# Nano-CC-EL_0v6_1_ENP252-17.net
KiCad netlist of a schematic drawn in EAGLE
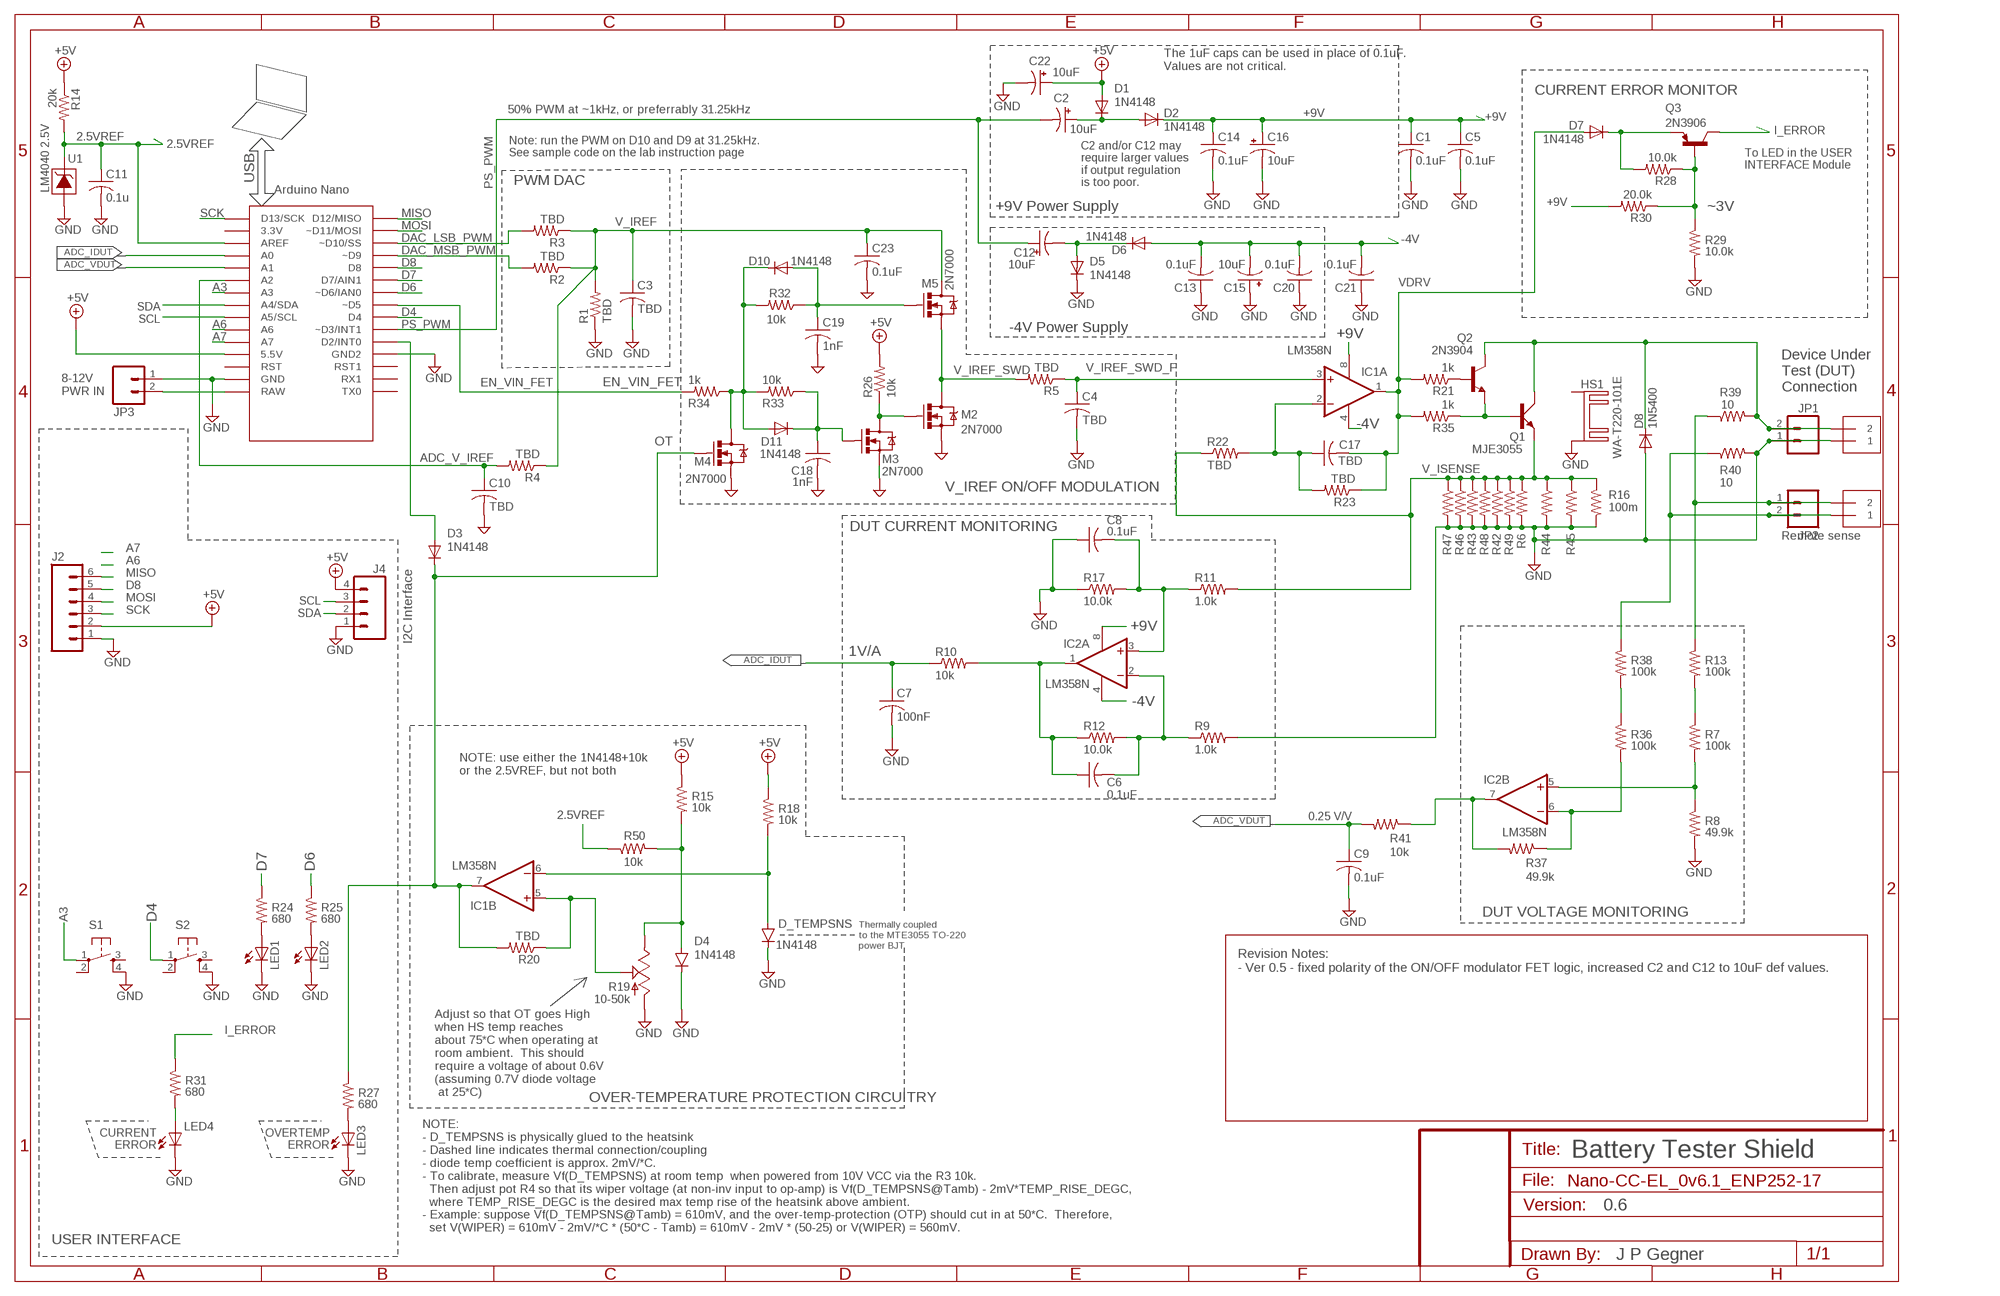
[diagram p0: schematic, sheet 1]

(export (version "E")
  (design (tool "Eeschema 10.0.6"))
  (components
    (comp (ref "C1")
      (value "0.1uF")
      (footprint "eagle-import:C025-025X050")
      (libsource (lib "eagle-import") (part "C-US025-025X050"))
    )
    (comp (ref "C2")
      (value "10uF")
      (footprint "eagle-import:E5-5")
      (libsource (lib "eagle-import") (part "CPOL-USE5-5"))
    )
    (comp (ref "C3")
      (value "TBD")
      (footprint "eagle-import:C025-025X050")
      (libsource (lib "eagle-import") (part "C-US025-025X050"))
    )
    (comp (ref "C4")
      (value "TBD")
      (footprint "eagle-import:C025-025X050")
      (libsource (lib "eagle-import") (part "C-US025-025X050"))
    )
    (comp (ref "C5")
      (value "0.1uF")
      (footprint "eagle-import:C025-025X050")
      (libsource (lib "eagle-import") (part "C-US025-025X050"))
    )
    (comp (ref "C6")
      (value "0.1uF")
      (footprint "eagle-import:C025-025X050")
      (libsource (lib "eagle-import") (part "C-US025-025X050"))
    )
    (comp (ref "C7")
      (value "100nF")
      (footprint "eagle-import:C025-024X044")
      (libsource (lib "eagle-import") (part "C-US025-024X044"))
    )
    (comp (ref "C8")
      (value "0.1uF")
      (footprint "eagle-import:C025-025X050")
      (libsource (lib "eagle-import") (part "C-US025-025X050"))
    )
    (comp (ref "C9")
      (value "0.1uF")
      (footprint "eagle-import:C025-025X050")
      (libsource (lib "eagle-import") (part "C-US025-025X050"))
    )
    (comp (ref "C10")
      (value "TBD")
      (footprint "eagle-import:C025-025X050")
      (libsource (lib "eagle-import") (part "C-US025-025X050"))
    )
    (comp (ref "C11")
      (value "0.1u")
      (footprint "eagle-import:C025-025X050")
      (libsource (lib "eagle-import") (part "C-US025-025X050"))
    )
    (comp (ref "C12")
      (value "10uF")
      (footprint "eagle-import:E5-5")
      (libsource (lib "eagle-import") (part "CPOL-USE5-5"))
    )
    (comp (ref "C13")
      (value "0.1uF")
      (footprint "eagle-import:C025-025X050")
      (libsource (lib "eagle-import") (part "C-US025-025X050"))
    )
    (comp (ref "C14")
      (value "0.1uF")
      (footprint "eagle-import:C025-025X050")
      (libsource (lib "eagle-import") (part "C-US025-025X050"))
    )
    (comp (ref "C15")
      (value "10uF")
      (footprint "eagle-import:E5-5")
      (libsource (lib "eagle-import") (part "CPOL-USE5-5"))
    )
    (comp (ref "C16")
      (value "10uF")
      (footprint "eagle-import:E5-5")
      (libsource (lib "eagle-import") (part "CPOL-USE5-5"))
    )
    (comp (ref "C17")
      (value "TBD")
      (footprint "eagle-import:C025-025X050")
      (libsource (lib "eagle-import") (part "C-US025-025X050"))
    )
    (comp (ref "C18")
      (value "1nF")
      (footprint "eagle-import:C025-025X050")
      (libsource (lib "eagle-import") (part "C-US025-025X050"))
    )
    (comp (ref "C19")
      (value "1nF")
      (footprint "eagle-import:C025-025X050")
      (libsource (lib "eagle-import") (part "C-US025-025X050"))
    )
    (comp (ref "C20")
      (value "0.1uF")
      (footprint "eagle-import:C025-025X050")
      (libsource (lib "eagle-import") (part "C-US025-025X050"))
    )
    (comp (ref "C21")
      (value "0.1uF")
      (footprint "eagle-import:C025-025X050")
      (libsource (lib "eagle-import") (part "C-US025-025X050"))
    )
    (comp (ref "C22")
      (value "10uF")
      (footprint "eagle-import:E5-5")
      (libsource (lib "eagle-import") (part "CPOL-USE5-5"))
    )
    (comp (ref "C23")
      (value "0.1uF")
      (footprint "eagle-import:C025-025X050")
      (libsource (lib "eagle-import") (part "C-US025-025X050"))
    )
    (comp (ref "D1")
      (value "1N4148")
      (footprint "eagle-import:0207_2V-D")
      (libsource (lib "eagle-import") (part "1N4148"))
    )
    (comp (ref "D2")
      (value "1N4148")
      (footprint "eagle-import:0207_2V-D")
      (libsource (lib "eagle-import") (part "1N4148"))
    )
    (comp (ref "D3")
      (value "1N4148")
      (footprint "eagle-import:0207_2V-D")
      (libsource (lib "eagle-import") (part "1N4148"))
    )
    (comp (ref "D4")
      (value "1N4148")
      (footprint "eagle-import:0207_2V-D")
      (libsource (lib "eagle-import") (part "ideal_elements_1N4148"))
    )
    (comp (ref "D5")
      (value "1N4148")
      (footprint "eagle-import:0207_2V-D")
      (libsource (lib "eagle-import") (part "1N4148"))
    )
    (comp (ref "D6")
      (value "1N4148")
      (footprint "eagle-import:0207_2V-D")
      (libsource (lib "eagle-import") (part "1N4148"))
    )
    (comp (ref "D7")
      (value "1N4148")
      (footprint "eagle-import:0207_2V-D")
      (libsource (lib "eagle-import") (part "1N4148"))
    )
    (comp (ref "D8")
      (value "1N5400")
      (footprint "eagle-import:DO201-15")
      (libsource (lib "eagle-import") (part "1N5400"))
    )
    (comp (ref "D10")
      (value "1N4148")
      (footprint "eagle-import:0207_2V-D")
      (libsource (lib "eagle-import") (part "1N4148"))
    )
    (comp (ref "D11")
      (value "1N4148")
      (footprint "eagle-import:0207_2V-D")
      (libsource (lib "eagle-import") (part "1N4148"))
    )
    (comp (ref "D_TEMPSNS")
      (value "1N4148")
      (footprint "eagle-import:0207_2V-D")
      (libsource (lib "eagle-import") (part "ideal_elements_1N4148"))
    )
    (comp (ref "HS1")
      (value "WA-T220-101E")
      (footprint "eagle-import:WX-T220-101E")
      (libsource (lib "eagle-import") (part "WA-T220-101E"))
    )
    (comp (ref "IC1")
      (value "LM358N")
      (footprint "eagle-import:DIL08")
      (libsource (lib "eagle-import") (part "LM358N"))
    )
    (comp (ref "IC2")
      (value "LM358N")
      (footprint "eagle-import:DIL08")
      (libsource (lib "eagle-import") (part "LM358N"))
    )
    (comp (ref "J2")
      (value "M06POLAR")
      (footprint "eagle-import:MOLEX-1X6")
      (libsource (lib "eagle-import") (part "M06POLAR"))
    )
    (comp (ref "J4")
      (value "M04LOCK_LONGPADS")
      (footprint "eagle-import:1X04_LOCK_LONGPADS")
      (libsource (lib "eagle-import") (part "M04LOCK_LONGPADS"))
    )
    (comp (ref "JP1")
      (value "M02PTH")
      (footprint "eagle-import:1X02")
      (libsource (lib "eagle-import") (part "M02PTH"))
    )
    (comp (ref "JP2")
      (value "M02PTH")
      (footprint "eagle-import:1X02")
      (libsource (lib "eagle-import") (part "M02PTH"))
    )
    (comp (ref "JP3")
      (value "M02PTH")
      (footprint "eagle-import:1X02")
      (libsource (lib "eagle-import") (part "M02PTH"))
    )
    (comp (ref "JP4")
      (value "1X2-3.5MM")
      (footprint "eagle-import:1X2-3.5MM")
      (libsource (lib "eagle-import") (part "1X2-3.5MM"))
    )
    (comp (ref "JP5")
      (value "1X2-3.5MM")
      (footprint "eagle-import:1X2-3.5MM")
      (libsource (lib "eagle-import") (part "1X2-3.5MM"))
    )
    (comp (ref "LED1")
      (value "LED-3MM-NO_SILK")
      (footprint "eagle-import:LED3MM-NS")
      (libsource (lib "eagle-import") (part "LED-3MM-NO_SILK"))
    )
    (comp (ref "LED2")
      (value "LED-3MM-NO_SILK")
      (footprint "eagle-import:LED3MM-NS")
      (libsource (lib "eagle-import") (part "LED-3MM-NO_SILK"))
    )
    (comp (ref "LED3")
      (value "LED-3MM-NO_SILK")
      (footprint "eagle-import:LED3MM-NS")
      (libsource (lib "eagle-import") (part "LED-3MM-NO_SILK"))
    )
    (comp (ref "LED4")
      (value "LED-3MM-NO_SILK")
      (footprint "eagle-import:LED3MM-NS")
      (libsource (lib "eagle-import") (part "LED-3MM-NO_SILK"))
    )
    (comp (ref "M2")
      (value "2N7000")
      (footprint "eagle-import:TO-92")
      (libsource (lib "eagle-import") (part "MOSFET-NCHANNEL2N7000"))
    )
    (comp (ref "M3")
      (value "2N7000")
      (footprint "eagle-import:TO-92")
      (libsource (lib "eagle-import") (part "MOSFET-NCHANNEL2N7000"))
    )
    (comp (ref "M4")
      (value "2N7000")
      (footprint "eagle-import:TO-92")
      (libsource (lib "eagle-import") (part "MOSFET-NCHANNEL2N7000"))
    )
    (comp (ref "M5")
      (value "2N7000")
      (footprint "eagle-import:TO-92")
      (libsource (lib "eagle-import") (part "MOSFET-NCHANNEL2N7000"))
    )
    (comp (ref "Q1")
      (value "MJE3055")
      (footprint "eagle-import:TO220AV")
      (libsource (lib "eagle-import") (part "MJE3055"))
    )
    (comp (ref "Q2")
      (value "2N3904")
      (footprint "eagle-import:TO92")
      (libsource (lib "eagle-import") (part "2N3904"))
    )
    (comp (ref "Q3")
      (value "2N3906")
      (footprint "eagle-import:TO92")
      (libsource (lib "eagle-import") (part "2N3906"))
    )
    (comp (ref "R1")
      (value "TBD")
      (footprint "eagle-import:0204_7")
      (libsource (lib "eagle-import") (part "R-US_0204/7"))
    )
    (comp (ref "R2")
      (value "TBD")
      (footprint "eagle-import:0204_7")
      (libsource (lib "eagle-import") (part "R-US_0204/7"))
    )
    (comp (ref "R3")
      (value "TBD")
      (footprint "eagle-import:0204_7")
      (libsource (lib "eagle-import") (part "R-US_0204/7"))
    )
    (comp (ref "R4")
      (value "TBD")
      (footprint "eagle-import:0204_7")
      (libsource (lib "eagle-import") (part "R-US_0204/7"))
    )
    (comp (ref "R5")
      (value "TBD")
      (footprint "eagle-import:0204V")
      (libsource (lib "eagle-import") (part "R-US_0204/2V"))
    )
    (comp (ref "R6")
      (value "100m")
      (footprint "eagle-import:0204_7")
      (libsource (lib "eagle-import") (part "R-US_0204/7"))
    )
    (comp (ref "R7")
      (value "100k")
      (footprint "eagle-import:0204_7")
      (libsource (lib "eagle-import") (part "R-US_0204/7"))
    )
    (comp (ref "R8")
      (value "49.9k")
      (footprint "eagle-import:0204_7")
      (libsource (lib "eagle-import") (part "R-US_0204/7"))
    )
    (comp (ref "R9")
      (value "1.0k")
      (footprint "eagle-import:0204_7")
      (libsource (lib "eagle-import") (part "R-US_0204/7"))
    )
    (comp (ref "R10")
      (value "10k")
      (footprint "eagle-import:0204_7")
      (libsource (lib "eagle-import") (part "R-US_0204/7"))
    )
    (comp (ref "R11")
      (value "1.0k")
      (footprint "eagle-import:0204_7")
      (libsource (lib "eagle-import") (part "R-US_0204/7"))
    )
    (comp (ref "R12")
      (value "10.0k")
      (footprint "eagle-import:0204V")
      (libsource (lib "eagle-import") (part "R-US_0204/2V"))
    )
    (comp (ref "R13")
      (value "100k")
      (footprint "eagle-import:0204_7")
      (libsource (lib "eagle-import") (part "R-US_0204/7"))
    )
    (comp (ref "R14")
      (value "20k")
      (footprint "eagle-import:0204_7")
      (libsource (lib "eagle-import") (part "R-US_0204/7"))
    )
    (comp (ref "R15")
      (value "10k")
      (footprint "eagle-import:0204_7")
      (libsource (lib "eagle-import") (part "R-US_0204/7"))
    )
    (comp (ref "R16")
      (value "100m")
      (footprint "eagle-import:0204_7")
      (libsource (lib "eagle-import") (part "R-US_0204/7"))
    )
    (comp (ref "R17")
      (value "10.0k")
      (footprint "eagle-import:0204_7")
      (libsource (lib "eagle-import") (part "R-US_0204/7"))
    )
    (comp (ref "R18")
      (value "10k")
      (footprint "eagle-import:0204_7")
      (libsource (lib "eagle-import") (part "R-US_0204/7"))
    )
    (comp (ref "R19")
      (value "10-50k")
      (footprint "eagle-import:B64Y")
      (libsource (lib "eagle-import") (part "TRIM_US-B64Y"))
    )
    (comp (ref "R20")
      (value "TBD")
      (footprint "eagle-import:0204_7")
      (libsource (lib "eagle-import") (part "R-US_0204/7"))
    )
    (comp (ref "R21")
      (value "1k")
      (footprint "eagle-import:0204_7")
      (libsource (lib "eagle-import") (part "R-US_0204/7"))
    )
    (comp (ref "R22")
      (value "TBD")
      (footprint "eagle-import:0204_7")
      (libsource (lib "eagle-import") (part "R-US_0204/7"))
    )
    (comp (ref "R23")
      (value "TBD")
      (footprint "eagle-import:0204V")
      (libsource (lib "eagle-import") (part "R-US_0204/2V"))
    )
    (comp (ref "R24")
      (value "680")
      (footprint "eagle-import:0204_7")
      (libsource (lib "eagle-import") (part "R-US_0204/7"))
    )
    (comp (ref "R25")
      (value "680")
      (footprint "eagle-import:0204_7")
      (libsource (lib "eagle-import") (part "R-US_0204/7"))
    )
    (comp (ref "R26")
      (value "10k")
      (footprint "eagle-import:0204_7")
      (libsource (lib "eagle-import") (part "R-US_0204/7"))
    )
    (comp (ref "R27")
      (value "680")
      (footprint "eagle-import:0204_7")
      (libsource (lib "eagle-import") (part "R-US_0204/7"))
    )
    (comp (ref "R28")
      (value "10.0k")
      (footprint "eagle-import:0204_7")
      (libsource (lib "eagle-import") (part "R-US_0204/7"))
    )
    (comp (ref "R29")
      (value "10.0k")
      (footprint "eagle-import:0204_7")
      (libsource (lib "eagle-import") (part "R-US_0204/7"))
    )
    (comp (ref "R30")
      (value "20.0k")
      (footprint "eagle-import:0204_7")
      (libsource (lib "eagle-import") (part "R-US_0204/7"))
    )
    (comp (ref "R31")
      (value "680")
      (footprint "eagle-import:0204_7")
      (libsource (lib "eagle-import") (part "R-US_0204/7"))
    )
    (comp (ref "R32")
      (value "10k")
      (footprint "eagle-import:0204_7")
      (libsource (lib "eagle-import") (part "R-US_0204/7"))
    )
    (comp (ref "R33")
      (value "10k")
      (footprint "eagle-import:0204_7")
      (libsource (lib "eagle-import") (part "R-US_0204/7"))
    )
    (comp (ref "R34")
      (value "1k")
      (footprint "eagle-import:0204V")
      (libsource (lib "eagle-import") (part "R-US_0204/2V"))
    )
    (comp (ref "R35")
      (value "1k")
      (footprint "eagle-import:0204_7")
      (libsource (lib "eagle-import") (part "R-US_0204/7"))
    )
    (comp (ref "R36")
      (value "100k")
      (footprint "eagle-import:0204_7")
      (libsource (lib "eagle-import") (part "R-US_0204/7"))
    )
    (comp (ref "R37")
      (value "49.9k")
      (footprint "eagle-import:0204V")
      (libsource (lib "eagle-import") (part "R-US_0204/2V"))
    )
    (comp (ref "R38")
      (value "100k")
      (footprint "eagle-import:0204_7")
      (libsource (lib "eagle-import") (part "R-US_0204/7"))
    )
    (comp (ref "R39")
      (value "10")
      (footprint "eagle-import:0204V")
      (libsource (lib "eagle-import") (part "R-US_0204/2V"))
    )
    (comp (ref "R40")
      (value "10")
      (footprint "eagle-import:0204V")
      (libsource (lib "eagle-import") (part "R-US_0204/2V"))
    )
    (comp (ref "R41")
      (value "10k")
      (footprint "eagle-import:0204_7")
      (libsource (lib "eagle-import") (part "R-US_0204/7"))
    )
    (comp (ref "R42")
      (value "100m")
      (footprint "eagle-import:0204_7")
      (libsource (lib "eagle-import") (part "R-US_0204/7"))
    )
    (comp (ref "R43")
      (value "100m")
      (footprint "eagle-import:0204_7")
      (libsource (lib "eagle-import") (part "R-US_0204/7"))
    )
    (comp (ref "R44")
      (value "100m")
      (footprint "eagle-import:0204_7")
      (libsource (lib "eagle-import") (part "R-US_0204/7"))
    )
    (comp (ref "R45")
      (value "100m")
      (footprint "eagle-import:0204_7")
      (libsource (lib "eagle-import") (part "R-US_0204/7"))
    )
    (comp (ref "R46")
      (value "100m")
      (footprint "eagle-import:0204_7")
      (libsource (lib "eagle-import") (part "R-US_0204/7"))
    )
    (comp (ref "R47")
      (value "100m")
      (footprint "eagle-import:0204_7")
      (libsource (lib "eagle-import") (part "R-US_0204/7"))
    )
    (comp (ref "R48")
      (value "100m")
      (footprint "eagle-import:0204_7")
      (libsource (lib "eagle-import") (part "R-US_0204/7"))
    )
    (comp (ref "R49")
      (value "100m")
      (footprint "eagle-import:0204_7")
      (libsource (lib "eagle-import") (part "R-US_0204/7"))
    )
    (comp (ref "R50")
      (value "10k")
      (footprint "eagle-import:0204_7")
      (libsource (lib "eagle-import") (part "R-US_0204/7"))
    )
    (comp (ref "S1")
      (value "E-SWITCH_TL1105L-F250-Q")
      (footprint "eagle-import:OMRON_B3F-1XX-JPGMOD")
      (libsource (lib "eagle-import") (part "E-SWITCH_TL1105L-F250-Q"))
    )
    (comp (ref "S2")
      (value "E-SWITCH_TL1105L-F250-Q")
      (footprint "eagle-import:OMRON_B3F-1XX-JPGMOD")
      (libsource (lib "eagle-import") (part "E-SWITCH_TL1105L-F250-Q"))
    )
    (comp (ref "U$1")
      (value "NANO")
      (footprint "eagle-import:NANO")
      (libsource (lib "eagle-import") (part "NANO"))
    )
    (comp (ref "U1")
      (value "LM4040 2.5V")
      (footprint "eagle-import:TO92")
      (libsource (lib "eagle-import") (part "LM4040TO92"))
    )
  )
  (nets
    (net (code "1") (name "+5V") (class "Default")
      (node (ref "C22") (pin "+") (pinfunction "+_+") (pintype "passive"))
      (node (ref "D1") (pin "A") (pinfunction "A_A") (pintype "passive"))
      (node (ref "J2") (pin "2") (pinfunction "2_2") (pintype "passive"))
      (node (ref "J4") (pin "4") (pinfunction "4_4") (pintype "passive"))
      (node (ref "R14") (pin "1") (pinfunction "1_1") (pintype "passive"))
      (node (ref "R15") (pin "1") (pinfunction "1_1") (pintype "passive"))
      (node (ref "R18") (pin "1") (pinfunction "1_1") (pintype "passive"))
      (node (ref "R26") (pin "2") (pinfunction "2_2") (pintype "passive"))
      (node (ref "U$1") (pin "5V") (pinfunction "5.5V_5V") (pintype "bidirectional"))
    )
    (net (code "2") (name "/+9V") (class "Default")
      (node (ref "C1") (pin "1") (pinfunction "1_1") (pintype "passive"))
      (node (ref "C14") (pin "1") (pinfunction "1_1") (pintype "passive"))
      (node (ref "C16") (pin "+") (pinfunction "+_+") (pintype "passive"))
      (node (ref "C5") (pin "1") (pinfunction "1_1") (pintype "passive"))
      (node (ref "D2") (pin "K") (pinfunction "C_K") (pintype "passive"))
      (node (ref "IC1") (pin "8") (pinfunction "V+_8") (pintype "power_in"))
      (node (ref "IC2") (pin "8") (pinfunction "V+_8") (pintype "power_in"))
      (node (ref "R30") (pin "2") (pinfunction "2_2") (pintype "passive"))
    )
    (net (code "3") (name "/-4V") (class "Default")
      (node (ref "C13") (pin "2") (pinfunction "2_2") (pintype "passive"))
      (node (ref "C15") (pin "-") (pinfunction "-_-") (pintype "passive"))
      (node (ref "C20") (pin "2") (pinfunction "2_2") (pintype "passive"))
      (node (ref "C21") (pin "2") (pinfunction "2_2") (pintype "passive"))
      (node (ref "D6") (pin "A") (pinfunction "A_A") (pintype "passive"))
      (node (ref "IC1") (pin "4") (pinfunction "V-_4") (pintype "power_in"))
      (node (ref "IC2") (pin "4") (pinfunction "V-_4") (pintype "power_in"))
    )
    (net (code "4") (name "/2.5VREF") (class "Default")
      (node (ref "C11") (pin "1") (pinfunction "1_1") (pintype "passive"))
      (node (ref "R14") (pin "2") (pinfunction "2_2") (pintype "passive"))
      (node (ref "R50") (pin "1") (pinfunction "1_1") (pintype "passive"))
      (node (ref "U$1") (pin "AREF") (pinfunction "AREF_AREF") (pintype "bidirectional"))
      (node (ref "U1") (pin "2") (pinfunction "CATHODE_2") (pintype "passive"))
    )
    (net (code "5") (name "/A3") (class "Default")
      (node (ref "S1") (pin "1") (pinfunction "P_1") (pintype "passive"))
      (node (ref "U$1") (pin "A3") (pinfunction "A3_A3") (pintype "bidirectional"))
    )
    (net (code "6") (name "/A6") (class "Default")
      (node (ref "U$1") (pin "A6") (pinfunction "A6_A6") (pintype "bidirectional"))
    )
    (net (code "7") (name "/A7") (class "Default")
      (node (ref "U$1") (pin "A7") (pinfunction "A7_A7") (pintype "bidirectional"))
    )
    (net (code "8") (name "/ADC_IDUT") (class "Default")
      (node (ref "C7") (pin "1") (pinfunction "1_1") (pintype "passive"))
      (node (ref "R10") (pin "1") (pinfunction "1_1") (pintype "passive"))
      (node (ref "U$1") (pin "A0") (pinfunction "A0_A0") (pintype "bidirectional"))
    )
    (net (code "9") (name "/ADC_VDUT") (class "Default")
      (node (ref "C9") (pin "1") (pinfunction "1_1") (pintype "passive"))
      (node (ref "R41") (pin "2") (pinfunction "2_2") (pintype "passive"))
      (node (ref "U$1") (pin "A1") (pinfunction "A1_A1") (pintype "bidirectional"))
    )
    (net (code "10") (name "/ADC_V_IREF") (class "Default")
      (node (ref "C10") (pin "1") (pinfunction "1_1") (pintype "passive"))
      (node (ref "R4") (pin "2") (pinfunction "2_2") (pintype "passive"))
      (node (ref "U$1") (pin "A2") (pinfunction "A2_A2") (pintype "bidirectional"))
    )
    (net (code "11") (name "/D4") (class "Default")
      (node (ref "S2") (pin "1") (pinfunction "P_1") (pintype "passive"))
      (node (ref "U$1") (pin "D4") (pinfunction "D4_D4") (pintype "bidirectional"))
    )
    (net (code "12") (name "/D6") (class "Default")
      (node (ref "R25") (pin "1") (pinfunction "1_1") (pintype "passive"))
      (node (ref "U$1") (pin "D6") (pinfunction "~{D6/IAN0}_D6") (pintype "bidirectional"))
    )
    (net (code "13") (name "/D7") (class "Default")
      (node (ref "R24") (pin "1") (pinfunction "1_1") (pintype "passive"))
      (node (ref "U$1") (pin "D7") (pinfunction "D7/AIN1_D7") (pintype "bidirectional"))
    )
    (net (code "14") (name "/D8") (class "Default")
      (node (ref "J2") (pin "5") (pinfunction "5_5") (pintype "passive"))
      (node (ref "U$1") (pin "D8") (pinfunction "D8_D8") (pintype "bidirectional"))
    )
    (net (code "15") (name "/DAC_LSB_PWM") (class "Default")
      (node (ref "R3") (pin "2") (pinfunction "2_2") (pintype "passive"))
      (node (ref "U$1") (pin "D10") (pinfunction "~{D10/SS}_D10") (pintype "bidirectional"))
    )
    (net (code "16") (name "/DAC_MSB_PWM") (class "Default")
      (node (ref "R2") (pin "2") (pinfunction "2_2") (pintype "passive"))
      (node (ref "U$1") (pin "D9") (pinfunction "~{D9}_D9") (pintype "bidirectional"))
    )
    (net (code "17") (name "/EN_VIN_FET") (class "Default")
      (node (ref "R34") (pin "2") (pinfunction "2_2") (pintype "passive"))
      (node (ref "U$1") (pin "D5") (pinfunction "~{D5}_D5") (pintype "bidirectional"))
    )
    (net (code "18") (name "/I_ERROR") (class "Default")
      (node (ref "Q3") (pin "1") (pinfunction "C_1") (pintype "passive"))
      (node (ref "R31") (pin "1") (pinfunction "1_1") (pintype "passive"))
    )
    (net (code "19") (name "/MISO") (class "Default")
      (node (ref "J2") (pin "6") (pinfunction "6_6") (pintype "passive"))
      (node (ref "U$1") (pin "D12") (pinfunction "D12/MISO_D12") (pintype "bidirectional"))
    )
    (net (code "20") (name "/MOSI") (class "Default")
      (node (ref "J2") (pin "4") (pinfunction "4_4") (pintype "passive"))
      (node (ref "U$1") (pin "D11") (pinfunction "~{D11/MOSI}_D11") (pintype "bidirectional"))
    )
    (net (code "21") (name "/OT") (class "Default")
      (node (ref "D3") (pin "K") (pinfunction "C_K") (pintype "passive"))
      (node (ref "IC1") (pin "7") (pinfunction "OUT_7") (pintype "output"))
      (node (ref "M4") (pin "2") (pinfunction "G_2") (pintype "passive"))
      (node (ref "R20") (pin "2") (pinfunction "2_2") (pintype "passive"))
      (node (ref "R27") (pin "1") (pinfunction "1_1") (pintype "passive"))
    )
    (net (code "22") (name "/PS_PWM") (class "Default")
      (node (ref "C12") (pin "+") (pinfunction "+_+") (pintype "passive"))
      (node (ref "C2") (pin "-") (pinfunction "-_-") (pintype "passive"))
      (node (ref "U$1") (pin "D3") (pinfunction "~{D3/INT1}_D3") (pintype "bidirectional"))
    )
    (net (code "23") (name "/SCK") (class "Default")
      (node (ref "J2") (pin "3") (pinfunction "3_3") (pintype "passive"))
      (node (ref "U$1") (pin "D13") (pinfunction "D13/SCK_D13") (pintype "bidirectional"))
    )
    (net (code "24") (name "/SCL") (class "Default")
      (node (ref "J4") (pin "3") (pinfunction "3_3") (pintype "passive"))
      (node (ref "U$1") (pin "A5") (pinfunction "A5/SCL_A5") (pintype "bidirectional"))
    )
    (net (code "25") (name "/SDA") (class "Default")
      (node (ref "J4") (pin "2") (pinfunction "2_2") (pintype "passive"))
      (node (ref "U$1") (pin "A4") (pinfunction "A4/SDA_A4") (pintype "bidirectional"))
    )
    (net (code "26") (name "/VDRV") (class "Default")
      (node (ref "C17") (pin "2") (pinfunction "2_2") (pintype "passive"))
      (node (ref "D7") (pin "A") (pinfunction "A_A") (pintype "passive"))
      (node (ref "IC1") (pin "1") (pinfunction "OUT_1") (pintype "output"))
      (node (ref "R21") (pin "2") (pinfunction "2_2") (pintype "passive"))
      (node (ref "R23") (pin "1") (pinfunction "1_1") (pintype "passive"))
      (node (ref "R35") (pin "2") (pinfunction "2_2") (pintype "passive"))
    )
    (net (code "27") (name "/V_IREF") (class "Default")
      (node (ref "C23") (pin "1") (pinfunction "1_1") (pintype "passive"))
      (node (ref "C3") (pin "1") (pinfunction "1_1") (pintype "passive"))
      (node (ref "M5") (pin "3") (pinfunction "D_3") (pintype "passive"))
      (node (ref "R1") (pin "2") (pinfunction "2_2") (pintype "passive"))
      (node (ref "R2") (pin "1") (pinfunction "1_1") (pintype "passive"))
      (node (ref "R3") (pin "1") (pinfunction "1_1") (pintype "passive"))
      (node (ref "R4") (pin "1") (pinfunction "1_1") (pintype "passive"))
    )
    (net (code "28") (name "/V_IREF_SWD") (class "Default")
      (node (ref "M2") (pin "3") (pinfunction "D_3") (pintype "passive"))
      (node (ref "M5") (pin "1") (pinfunction "S_1") (pintype "passive"))
      (node (ref "R5") (pin "2") (pinfunction "2_2") (pintype "passive"))
    )
    (net (code "29") (name "/V_IREF_SWD_F") (class "Default")
      (node (ref "C4") (pin "1") (pinfunction "1_1") (pintype "passive"))
      (node (ref "IC1") (pin "3") (pinfunction "+IN_3") (pintype "input"))
      (node (ref "R5") (pin "1") (pinfunction "1_1") (pintype "passive"))
    )
    (net (code "30") (name "/V_ISENSE") (class "Default")
      (node (ref "Q1") (pin "E") (pinfunction "E_E") (pintype "passive"))
      (node (ref "R11") (pin "2") (pinfunction "2_2") (pintype "passive"))
      (node (ref "R16") (pin "1") (pinfunction "1_1") (pintype "passive"))
      (node (ref "R22") (pin "1") (pinfunction "1_1") (pintype "passive"))
      (node (ref "R42") (pin "1") (pinfunction "1_1") (pintype "passive"))
      (node (ref "R43") (pin "1") (pinfunction "1_1") (pintype "passive"))
      (node (ref "R44") (pin "1") (pinfunction "1_1") (pintype "passive"))
      (node (ref "R45") (pin "1") (pinfunction "1_1") (pintype "passive"))
      (node (ref "R46") (pin "1") (pinfunction "1_1") (pintype "passive"))
      (node (ref "R47") (pin "1") (pinfunction "1_1") (pintype "passive"))
      (node (ref "R48") (pin "1") (pinfunction "1_1") (pintype "passive"))
      (node (ref "R49") (pin "1") (pinfunction "1_1") (pintype "passive"))
      (node (ref "R6") (pin "1") (pinfunction "1_1") (pintype "passive"))
    )
    (net (code "31") (name "GND") (class "Default")
      (node (ref "C1") (pin "2") (pinfunction "2_2") (pintype "passive"))
      (node (ref "C10") (pin "2") (pinfunction "2_2") (pintype "passive"))
      (node (ref "C11") (pin "2") (pinfunction "2_2") (pintype "passive"))
      (node (ref "C13") (pin "1") (pinfunction "1_1") (pintype "passive"))
      (node (ref "C14") (pin "2") (pinfunction "2_2") (pintype "passive"))
      (node (ref "C15") (pin "+") (pinfunction "+_+") (pintype "passive"))
      (node (ref "C16") (pin "-") (pinfunction "-_-") (pintype "passive"))
      (node (ref "C18") (pin "2") (pinfunction "2_2") (pintype "passive"))
      (node (ref "C19") (pin "2") (pinfunction "2_2") (pintype "passive"))
      (node (ref "C20") (pin "1") (pinfunction "1_1") (pintype "passive"))
      (node (ref "C21") (pin "1") (pinfunction "1_1") (pintype "passive"))
      (node (ref "C22") (pin "-") (pinfunction "-_-") (pintype "passive"))
      (node (ref "C23") (pin "2") (pinfunction "2_2") (pintype "passive"))
      (node (ref "C3") (pin "2") (pinfunction "2_2") (pintype "passive"))
      (node (ref "C4") (pin "2") (pinfunction "2_2") (pintype "passive"))
      (node (ref "C5") (pin "2") (pinfunction "2_2") (pintype "passive"))
      (node (ref "C7") (pin "2") (pinfunction "2_2") (pintype "passive"))
      (node (ref "C8") (pin "1") (pinfunction "1_1") (pintype "passive"))
      (node (ref "C9") (pin "2") (pinfunction "2_2") (pintype "passive"))
      (node (ref "D4") (pin "K") (pinfunction "C_K") (pintype "passive"))
      (node (ref "D5") (pin "K") (pinfunction "C_K") (pintype "passive"))
      (node (ref "D8") (pin "A") (pinfunction "A_A") (pintype "passive"))
      (node (ref "D_TEMPSNS") (pin "K") (pinfunction "C_K") (pintype "passive"))
      (node (ref "HS1") (pin "K2") (pinfunction "K_K2") (pintype "passive"))
      (node (ref "J2") (pin "1") (pinfunction "1_1") (pintype "passive"))
      (node (ref "J4") (pin "1") (pinfunction "1_1") (pintype "passive"))
      (node (ref "JP1") (pin "1") (pinfunction "1_1") (pintype "passive"))
      (node (ref "JP3") (pin "1") (pinfunction "1_1") (pintype "passive"))
      (node (ref "JP5") (pin "1") (pinfunction "1_1") (pintype "passive"))
      (node (ref "LED1") (pin "K") (pinfunction "C_K") (pintype "passive"))
      (node (ref "LED2") (pin "K") (pinfunction "C_K") (pintype "passive"))
      (node (ref "LED3") (pin "K") (pinfunction "C_K") (pintype "passive"))
      (node (ref "LED4") (pin "K") (pinfunction "C_K") (pintype "passive"))
      (node (ref "M2") (pin "1") (pinfunction "S_1") (pintype "passive"))
      (node (ref "M3") (pin "1") (pinfunction "S_1") (pintype "passive"))
      (node (ref "M4") (pin "1") (pinfunction "S_1") (pintype "passive"))
      (node (ref "R1") (pin "1") (pinfunction "1_1") (pintype "passive"))
      (node (ref "R16") (pin "2") (pinfunction "2_2") (pintype "passive"))
      (node (ref "R17") (pin "1") (pinfunction "1_1") (pintype "passive"))
      (node (ref "R19") (pin "A") (pinfunction "A_A") (pintype "passive"))
      (node (ref "R29") (pin "2") (pinfunction "2_2") (pintype "passive"))
      (node (ref "R40") (pin "2") (pinfunction "2_2") (pintype "passive"))
      (node (ref "R42") (pin "2") (pinfunction "2_2") (pintype "passive"))
      (node (ref "R43") (pin "2") (pinfunction "2_2") (pintype "passive"))
      (node (ref "R44") (pin "2") (pinfunction "2_2") (pintype "passive"))
      (node (ref "R45") (pin "2") (pinfunction "2_2") (pintype "passive"))
      (node (ref "R46") (pin "2") (pinfunction "2_2") (pintype "passive"))
      (node (ref "R47") (pin "2") (pinfunction "2_2") (pintype "passive"))
      (node (ref "R48") (pin "2") (pinfunction "2_2") (pintype "passive"))
      (node (ref "R49") (pin "2") (pinfunction "2_2") (pintype "passive"))
      (node (ref "R6") (pin "2") (pinfunction "2_2") (pintype "passive"))
      (node (ref "R8") (pin "2") (pinfunction "2_2") (pintype "passive"))
      (node (ref "R9") (pin "2") (pinfunction "2_2") (pintype "passive"))
      (node (ref "S1") (pin "4") (pinfunction "S1_4") (pintype "passive"))
      (node (ref "S2") (pin "4") (pinfunction "S1_4") (pintype "passive"))
      (node (ref "U$1") (pin "GND") (pinfunction "GND_GND") (pintype "bidirectional"))
      (node (ref "U$1") (pin "GND1") (pinfunction "GND2_GND1") (pintype "bidirectional"))
      (node (ref "U1") (pin "3") (pinfunction "ANODE_3") (pintype "passive"))
    )
    (net (code "32") (name "Net-(D1-C)") (class "Default")
      (node (ref "C2") (pin "+") (pinfunction "+_+") (pintype "passive"))
      (node (ref "D1") (pin "K") (pinfunction "C_K") (pintype "passive"))
      (node (ref "D2") (pin "A") (pinfunction "A_A") (pintype "passive"))
    )
    (net (code "33") (name "Net-(D4-PadA)") (class "Default")
      (node (ref "D4") (pin "A") (pinfunction "A_A") (pintype "passive"))
      (node (ref "R15") (pin "2") (pinfunction "2_2") (pintype "passive"))
      (node (ref "R19") (pin "E") (pinfunction "E_E") (pintype "passive"))
      (node (ref "R50") (pin "2") (pinfunction "2_2") (pintype "passive"))
    )
    (net (code "34") (name "Net-(D6-C)") (class "Default")
      (node (ref "C12") (pin "-") (pinfunction "-_-") (pintype "passive"))
      (node (ref "D5") (pin "A") (pinfunction "A_A") (pintype "passive"))
      (node (ref "D6") (pin "K") (pinfunction "C_K") (pintype "passive"))
    )
    (net (code "35") (name "Net-(D7-C)") (class "Default")
      (node (ref "D7") (pin "K") (pinfunction "C_K") (pintype "passive"))
      (node (ref "Q3") (pin "3") (pinfunction "E_3") (pintype "passive"))
      (node (ref "R28") (pin "2") (pinfunction "2_2") (pintype "passive"))
    )
    (net (code "36") (name "Net-(D10-C)") (class "Default")
      (node (ref "D10") (pin "K") (pinfunction "C_K") (pintype "passive"))
      (node (ref "D11") (pin "A") (pinfunction "A_A") (pintype "passive"))
      (node (ref "M4") (pin "3") (pinfunction "D_3") (pintype "passive"))
      (node (ref "R32") (pin "2") (pinfunction "2_2") (pintype "passive"))
      (node (ref "R33") (pin "2") (pinfunction "2_2") (pintype "passive"))
      (node (ref "R34") (pin "1") (pinfunction "1_1") (pintype "passive"))
    )
    (net (code "37") (name "Net-(D11-C)") (class "Default")
      (node (ref "C18") (pin "1") (pinfunction "1_1") (pintype "passive"))
      (node (ref "D11") (pin "K") (pinfunction "C_K") (pintype "passive"))
      (node (ref "M3") (pin "2") (pinfunction "G_2") (pintype "passive"))
      (node (ref "R33") (pin "1") (pinfunction "1_1") (pintype "passive"))
    )
    (net (code "38") (name "Net-(IC1A--IN)") (class "Default")
      (node (ref "C17") (pin "1") (pinfunction "1_1") (pintype "passive"))
      (node (ref "IC1") (pin "2") (pinfunction "-IN_2") (pintype "input"))
      (node (ref "R22") (pin "2") (pinfunction "2_2") (pintype "passive"))
      (node (ref "R23") (pin "2") (pinfunction "2_2") (pintype "passive"))
    )
    (net (code "39") (name "Net-(IC1B-+IN)") (class "Default")
      (node (ref "IC1") (pin "5") (pinfunction "+IN_5") (pintype "input"))
      (node (ref "R19") (pin "S") (pinfunction "S_S") (pintype "passive"))
      (node (ref "R20") (pin "1") (pinfunction "1_1") (pintype "passive"))
    )
    (net (code "40") (name "Net-(IC1B--IN)") (class "Default")
      (node (ref "D_TEMPSNS") (pin "A") (pinfunction "A_A") (pintype "passive"))
      (node (ref "IC1") (pin "6") (pinfunction "-IN_6") (pintype "input"))
      (node (ref "R18") (pin "2") (pinfunction "2_2") (pintype "passive"))
    )
    (net (code "41") (name "Net-(IC2A-+IN)") (class "Default")
      (node (ref "C8") (pin "2") (pinfunction "2_2") (pintype "passive"))
      (node (ref "IC2") (pin "3") (pinfunction "+IN_3") (pintype "input"))
      (node (ref "R11") (pin "1") (pinfunction "1_1") (pintype "passive"))
      (node (ref "R17") (pin "2") (pinfunction "2_2") (pintype "passive"))
    )
    (net (code "42") (name "Net-(IC2A--IN)") (class "Default")
      (node (ref "C6") (pin "2") (pinfunction "2_2") (pintype "passive"))
      (node (ref "IC2") (pin "2") (pinfunction "-IN_2") (pintype "input"))
      (node (ref "R12") (pin "2") (pinfunction "2_2") (pintype "passive"))
      (node (ref "R9") (pin "1") (pinfunction "1_1") (pintype "passive"))
    )
    (net (code "43") (name "Net-(IC2A-OUT)") (class "Default")
      (node (ref "C6") (pin "1") (pinfunction "1_1") (pintype "passive"))
      (node (ref "IC2") (pin "1") (pinfunction "OUT_1") (pintype "output"))
      (node (ref "R10") (pin "2") (pinfunction "2_2") (pintype "passive"))
      (node (ref "R12") (pin "1") (pinfunction "1_1") (pintype "passive"))
    )
    (net (code "44") (name "Net-(IC2B-+IN)") (class "Default")
      (node (ref "IC2") (pin "5") (pinfunction "+IN_5") (pintype "input"))
      (node (ref "R7") (pin "2") (pinfunction "2_2") (pintype "passive"))
      (node (ref "R8") (pin "1") (pinfunction "1_1") (pintype "passive"))
    )
    (net (code "45") (name "Net-(IC2B--IN)") (class "Default")
      (node (ref "IC2") (pin "6") (pinfunction "-IN_6") (pintype "input"))
      (node (ref "R36") (pin "2") (pinfunction "2_2") (pintype "passive"))
      (node (ref "R37") (pin "1") (pinfunction "1_1") (pintype "passive"))
    )
    (net (code "46") (name "Net-(IC2B-OUT)") (class "Default")
      (node (ref "IC2") (pin "7") (pinfunction "OUT_7") (pintype "output"))
      (node (ref "R37") (pin "2") (pinfunction "2_2") (pintype "passive"))
      (node (ref "R41") (pin "1") (pinfunction "1_1") (pintype "passive"))
    )
    (net (code "47") (name "Net-(JP2-Pad1)") (class "Default")
      (node (ref "JP2") (pin "1") (pinfunction "1_1") (pintype "passive"))
      (node (ref "JP4") (pin "2") (pinfunction "2_2") (pintype "passive"))
      (node (ref "R13") (pin "1") (pinfunction "1_1") (pintype "passive"))
      (node (ref "R39") (pin "1") (pinfunction "1_1") (pintype "passive"))
    )
    (net (code "48") (name "Net-(JP2-Pad2)") (class "Default")
      (node (ref "JP2") (pin "2") (pinfunction "2_2") (pintype "passive"))
      (node (ref "JP4") (pin "1") (pinfunction "1_1") (pintype "passive"))
      (node (ref "R38") (pin "1") (pinfunction "1_1") (pintype "passive"))
      (node (ref "R40") (pin "1") (pinfunction "1_1") (pintype "passive"))
    )
    (net (code "49") (name "Net-(JP3-Pad2)") (class "Default")
      (node (ref "JP3") (pin "2") (pinfunction "2_2") (pintype "passive"))
      (node (ref "U$1") (pin "RAW") (pinfunction "RAW_RAW") (pintype "bidirectional"))
    )
    (net (code "50") (name "Net-(LED1-PadA)") (class "Default")
      (node (ref "LED1") (pin "A") (pinfunction "A_A") (pintype "passive"))
      (node (ref "R24") (pin "2") (pinfunction "2_2") (pintype "passive"))
    )
    (net (code "51") (name "Net-(LED2-PadA)") (class "Default")
      (node (ref "LED2") (pin "A") (pinfunction "A_A") (pintype "passive"))
      (node (ref "R25") (pin "2") (pinfunction "2_2") (pintype "passive"))
    )
    (net (code "52") (name "Net-(LED3-PadA)") (class "Default")
      (node (ref "LED3") (pin "A") (pinfunction "A_A") (pintype "passive"))
      (node (ref "R27") (pin "2") (pinfunction "2_2") (pintype "passive"))
    )
    (net (code "53") (name "Net-(LED4-PadA)") (class "Default")
      (node (ref "LED4") (pin "A") (pinfunction "A_A") (pintype "passive"))
      (node (ref "R31") (pin "2") (pinfunction "2_2") (pintype "passive"))
    )
    (net (code "54") (name "Net-(M2-G)") (class "Default")
      (node (ref "M2") (pin "2") (pinfunction "G_2") (pintype "passive"))
      (node (ref "M3") (pin "3") (pinfunction "D_3") (pintype "passive"))
      (node (ref "R26") (pin "1") (pinfunction "1_1") (pintype "passive"))
    )
    (net (code "55") (name "Net-(M5-G)") (class "Default")
      (node (ref "C19") (pin "1") (pinfunction "1_1") (pintype "passive"))
      (node (ref "D10") (pin "A") (pinfunction "A_A") (pintype "passive"))
      (node (ref "M5") (pin "2") (pinfunction "G_2") (pintype "passive"))
      (node (ref "R32") (pin "1") (pinfunction "1_1") (pintype "passive"))
    )
    (net (code "56") (name "Net-(Q2-B)") (class "Default")
      (node (ref "Q2") (pin "2") (pinfunction "B_2") (pintype "passive"))
      (node (ref "R21") (pin "1") (pinfunction "1_1") (pintype "passive"))
    )
    (net (code "57") (name "Net-(Q2-C)") (class "Default")
      (node (ref "D8") (pin "C") (pinfunction "C_C") (pintype "passive"))
      (node (ref "JP1") (pin "2") (pinfunction "2_2") (pintype "passive"))
      (node (ref "JP5") (pin "2") (pinfunction "2_2") (pintype "passive"))
      (node (ref "Q1") (pin "C") (pinfunction "C_C") (pintype "passive"))
      (node (ref "Q2") (pin "1") (pinfunction "C_1") (pintype "passive"))
      (node (ref "R39") (pin "2") (pinfunction "2_2") (pintype "passive"))
    )
    (net (code "58") (name "Net-(Q2-E)") (class "Default")
      (node (ref "Q1") (pin "B") (pinfunction "B_B") (pintype "passive"))
      (node (ref "Q2") (pin "3") (pinfunction "E_3") (pintype "passive"))
      (node (ref "R35") (pin "1") (pinfunction "1_1") (pintype "passive"))
    )
    (net (code "59") (name "Net-(Q3-B)") (class "Default")
      (node (ref "Q3") (pin "2") (pinfunction "B_2") (pintype "passive"))
      (node (ref "R28") (pin "1") (pinfunction "1_1") (pintype "passive"))
      (node (ref "R29") (pin "1") (pinfunction "1_1") (pintype "passive"))
      (node (ref "R30") (pin "1") (pinfunction "1_1") (pintype "passive"))
    )
    (net (code "60") (name "Net-(R13-Pad2)") (class "Default")
      (node (ref "R13") (pin "2") (pinfunction "2_2") (pintype "passive"))
      (node (ref "R7") (pin "1") (pinfunction "1_1") (pintype "passive"))
    )
    (net (code "61") (name "Net-(R36-Pad1)") (class "Default")
      (node (ref "R36") (pin "1") (pinfunction "1_1") (pintype "passive"))
      (node (ref "R38") (pin "2") (pinfunction "2_2") (pintype "passive"))
    )
    (net (code "62") (name "Net-(U$1-D2{slash}INT0)") (class "Default")
      (node (ref "D3") (pin "A") (pinfunction "A_A") (pintype "passive"))
      (node (ref "U$1") (pin "D2") (pinfunction "D2/INT0_D2") (pintype "bidirectional"))
    )
    (net (code "63") (name "unconnected-(HS1-K-PadK1)") (class "Default")
      (node (ref "HS1") (pin "K1") (pinfunction "K_K1") (pintype "passive"))
    )
    (net (code "64") (name "unconnected-(S1-P1-Pad2)") (class "Default")
      (node (ref "S1") (pin "2") (pinfunction "P1_2") (pintype "passive"))
    )
    (net (code "65") (name "unconnected-(S1-S-Pad3)") (class "Default")
      (node (ref "S1") (pin "3") (pinfunction "S_3") (pintype "passive"))
    )
    (net (code "66") (name "unconnected-(S2-P1-Pad2)") (class "Default")
      (node (ref "S2") (pin "2") (pinfunction "P1_2") (pintype "passive"))
    )
    (net (code "67") (name "unconnected-(S2-S-Pad3)") (class "Default")
      (node (ref "S2") (pin "3") (pinfunction "S_3") (pintype "passive"))
    )
    (net (code "68") (name "unconnected-(U$1-Pad3.3V)") (class "Default")
      (node (ref "U$1") (pin "3.3V") (pinfunction "3.3V_3.3V") (pintype "bidirectional"))
    )
    (net (code "69") (name "unconnected-(U$1-PadICSP1)") (class "Default")
      (node (ref "U$1") (pin "ICSP1") (pinfunction "ICSP1_ICSP1") (pintype "bidirectional"))
    )
    (net (code "70") (name "unconnected-(U$1-PadICSP2)") (class "Default")
      (node (ref "U$1") (pin "ICSP2") (pinfunction "ICSP2_ICSP2") (pintype "bidirectional"))
    )
    (net (code "71") (name "unconnected-(U$1-PadICSP3)") (class "Default")
      (node (ref "U$1") (pin "ICSP3") (pinfunction "ICSP3_ICSP3") (pintype "bidirectional"))
    )
    (net (code "72") (name "unconnected-(U$1-PadICSP4)") (class "Default")
      (node (ref "U$1") (pin "ICSP4") (pinfunction "ICSP4_ICSP4") (pintype "bidirectional"))
    )
    (net (code "73") (name "unconnected-(U$1-PadICSP5)") (class "Default")
      (node (ref "U$1") (pin "ICSP5") (pinfunction "ICSP5_ICSP5") (pintype "bidirectional"))
    )
    (net (code "74") (name "unconnected-(U$1-PadICSP6)") (class "Default")
      (node (ref "U$1") (pin "ICSP6") (pinfunction "ICSP6_ICSP6") (pintype "bidirectional"))
    )
    (net (code "75") (name "unconnected-(U$1-PadRST)") (class "Default")
      (node (ref "U$1") (pin "RST") (pinfunction "RST_RST") (pintype "bidirectional"))
    )
    (net (code "76") (name "unconnected-(U$1-PadRST1)") (class "Default")
      (node (ref "U$1") (pin "RST1") (pinfunction "RST1_RST1") (pintype "bidirectional"))
    )
    (net (code "77") (name "unconnected-(U$1-PadRX1)") (class "Default")
      (node (ref "U$1") (pin "RX1") (pinfunction "RX1_RX1") (pintype "bidirectional"))
    )
    (net (code "78") (name "unconnected-(U$1-PadTX0)") (class "Default")
      (node (ref "U$1") (pin "TX0") (pinfunction "TX0_TX0") (pintype "bidirectional"))
    )
  )
)
